# Follow_Line_Robot_Controller_Shematic.net
KiCad netlist of a schematic drawn in Altium Designer
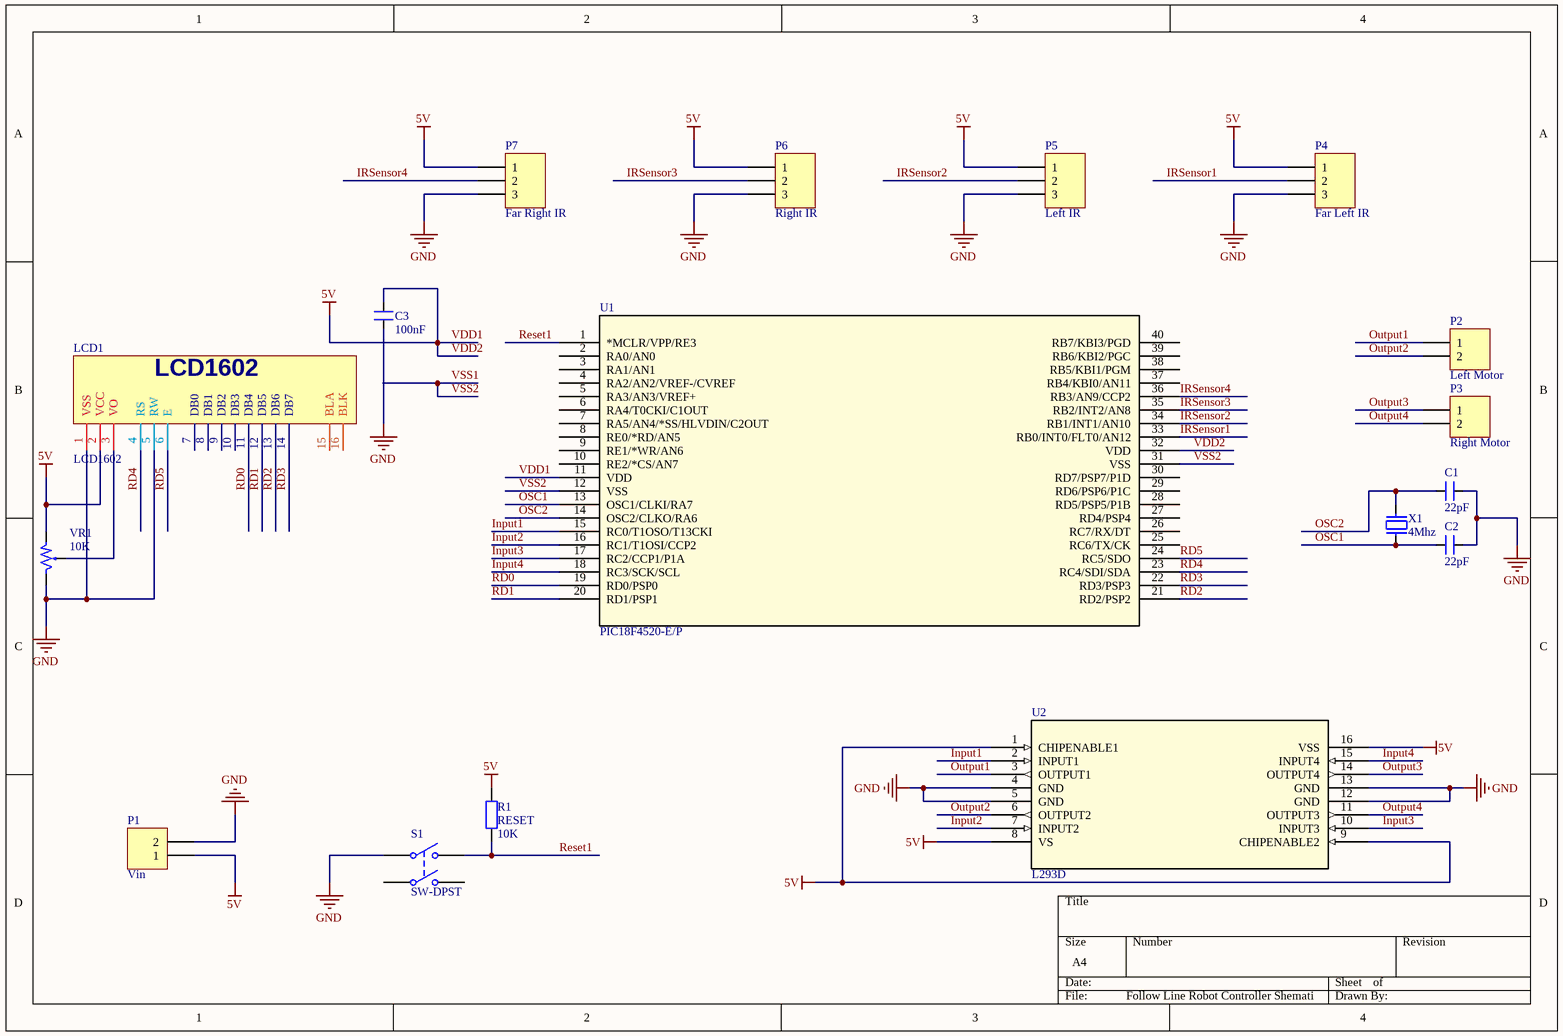
[diagram p0: Follow Line Robot Controller Shematic.SchDoc]

(export (version "E")
  (design (tool "Eeschema 10.0.6"))
  (components
    (comp (ref "C1")
      (value "22pF")
      (footprint "CN3")
      (description "Cap np W0.3")
      (fields (field (name "Comment") "Cap Cer"))
      (libsource (lib "Composants_Projet_Sheet_Full") (part "CN3"))
    )
    (comp (ref "C2")
      (value "22pF")
      (footprint "CN3")
      (description "Cap np W0.3")
      (fields (field (name "Comment") "Cap Cer"))
      (libsource (lib "Composants_Projet_Sheet_Full") (part "CN3"))
    )
    (comp (ref "C3")
      (value "100nF")
      (footprint "CN3")
      (description "Cap np W0.3")
      (fields (field (name "Comment") "Cap Cer"))
      (libsource (lib "Composants_Projet_Sheet_Full") (part "CN3"))
    )
    (comp (ref "LCD1")
      (value "LCD1602")
      (footprint "LCD1602")
      (libsource (lib "Composants_Projet_Sheet_Full") (part "LCD1602"))
    )
    (comp (ref "P1")
      (value "Vin")
      (footprint "HDR1X2")
      (description "Header, 2-Pin")
      (fields (field (name "PUBLISHER") "Altium Limited"))
      (libsource (lib "Composants_Projet_Sheet_Full") (part "Header 2"))
    )
    (comp (ref "P2")
      (value "Left Motor")
      (footprint "HDR1X2")
      (description "Header, 2-Pin")
      (fields (field (name "PUBLISHER") "Altium Limited"))
      (libsource (lib "") (part "Header 2_1"))
    )
    (comp (ref "P3")
      (value "Right Motor")
      (footprint "HDR1X2")
      (description "Header, 2-Pin")
      (fields (field (name "PUBLISHER") "Altium Limited"))
      (libsource (lib "") (part "Header 2_1"))
    )
    (comp (ref "P4")
      (value "Far Left IR")
      (footprint "HDR1X3")
      (description "Header, 3-Pin")
      (fields (field (name "PUBLISHER") "Altium Limited"))
      (libsource (lib "Composants_Projet_Sheet_Full") (part "Header 3"))
    )
    (comp (ref "P5")
      (value "Left IR")
      (footprint "HDR1X3")
      (description "Header, 3-Pin")
      (fields (field (name "PUBLISHER") "Altium Limited"))
      (libsource (lib "Composants_Projet_Sheet_Full") (part "Header 3"))
    )
    (comp (ref "P6")
      (value "Right IR")
      (footprint "HDR1X3")
      (description "Header, 3-Pin")
      (fields (field (name "PUBLISHER") "Altium Limited"))
      (libsource (lib "Composants_Projet_Sheet_Full") (part "Header 3"))
    )
    (comp (ref "P7")
      (value "Far Right IR")
      (footprint "HDR1X3")
      (description "Header, 3-Pin")
      (fields (field (name "PUBLISHER") "Altium Limited"))
      (libsource (lib "Composants_Projet_Sheet_Full") (part "Header 3"))
    )
    (comp (ref "R1")
      (value "RESET")
      (footprint "SMD R1206")
      (description "Resistor")
      (fields (field (name "ALTIUM_VALUE") "10K") (field (name "PUBLISHER") "Altium Limited"))
      (libsource (lib "Composants_Projet_Sheet_Full") (part "Res2_1"))
    )
    (comp (ref "S1")
      (value "SW-DPST")
      (footprint "DPST-4")
      (description "Double-Pole, Single-Throw Switch")
      (fields (field (name "PUBLISHER") "Altium Limited"))
      (libsource (lib "Composants_Projet_Sheet_Full") (part "SW-DPST"))
    )
    (comp (ref "U1")
      (value "PIC18F4520-E/P")
      (footprint "PDIP40_600MC_MCH")
      (description "No Description Available")
      (fields (field (name "COPYRIGHT") "Copyright (C) 2022 Ultra Librarian. All rights reserved."))
      (libsource (lib "PIC18F4520-E&slash_P") (part "PIC18F4520-E/P"))
    )
    (comp (ref "U2")
      (value "L293D")
      (footprint "PowerDIP-16_STM")
      (description "No Description Available")
      (fields (field (name "COPYRIGHT") "Copyright (C) 2022 Ultra Librarian. All rights reserved."))
      (libsource (lib "L293D") (part "L293D"))
    )
    (comp (ref "VR1")
      (value "10K")
      (footprint "VR")
      (description "Var Resistor")
      (libsource (lib "Composants_Projet_Sheet_Full") (part "VR1"))
    )
    (comp (ref "X1")
      (value "4Mhz")
      (footprint "XT2")
      (description "Crystal For all Crystal 2pin.")
      (libsource (lib "Composants_Projet_Sheet_Full") (part "XT2"))
    )
  )
  (nets
    (net (code "1") (name "/IRSensor1") (class "Default")
      (node (ref "P4") (pin "2") (pinfunction "2_2") (pintype "passive"))
      (node (ref "U1") (pin "33") (pinfunction "RB0/INT0/FLT0/AN12_33") (pintype "passive"))
    )
    (net (code "2") (name "/IRSensor2") (class "Default")
      (node (ref "P5") (pin "2") (pinfunction "2_2") (pintype "passive"))
      (node (ref "U1") (pin "34") (pinfunction "RB1/INT1/AN10_34") (pintype "passive"))
    )
    (net (code "3") (name "/IRSensor3") (class "Default")
      (node (ref "P6") (pin "2") (pinfunction "2_2") (pintype "passive"))
      (node (ref "U1") (pin "35") (pinfunction "RB2/INT2/AN8_35") (pintype "passive"))
    )
    (net (code "4") (name "/IRSensor4") (class "Default")
      (node (ref "P7") (pin "2") (pinfunction "2_2") (pintype "passive"))
      (node (ref "U1") (pin "36") (pinfunction "RB3/AN9/CCP2_36") (pintype "passive"))
    )
    (net (code "5") (name "/Input1") (class "Default")
      (node (ref "U1") (pin "15") (pinfunction "RC0/T1OSO/T13CKI_15") (pintype "passive"))
      (node (ref "U2") (pin "2") (pinfunction "INPUT1_2") (pintype "input"))
    )
    (net (code "6") (name "/Input2") (class "Default")
      (node (ref "U1") (pin "16") (pinfunction "RC1/T1OSI/CCP2_16") (pintype "passive"))
      (node (ref "U2") (pin "7") (pinfunction "INPUT2_7") (pintype "input"))
    )
    (net (code "7") (name "/Input3") (class "Default")
      (node (ref "U1") (pin "17") (pinfunction "RC2/CCP1/P1A_17") (pintype "passive"))
      (node (ref "U2") (pin "10") (pinfunction "INPUT3_10") (pintype "input"))
    )
    (net (code "8") (name "/Input4") (class "Default")
      (node (ref "U1") (pin "18") (pinfunction "RC3/SCK/SCL_18") (pintype "passive"))
      (node (ref "U2") (pin "15") (pinfunction "INPUT4_15") (pintype "input"))
    )
    (net (code "9") (name "/OSC1") (class "Default")
      (node (ref "C2") (pin "1") (pinfunction "1_1") (pintype "passive"))
      (node (ref "U1") (pin "13") (pinfunction "OSC1/CLKI/RA7_13") (pintype "passive"))
      (node (ref "X1") (pin "1") (pinfunction "1_1") (pintype "passive"))
    )
    (net (code "10") (name "/OSC2") (class "Default")
      (node (ref "C1") (pin "1") (pinfunction "1_1") (pintype "passive"))
      (node (ref "U1") (pin "14") (pinfunction "OSC2/CLKO/RA6_14") (pintype "passive"))
      (node (ref "X1") (pin "2") (pinfunction "2_2") (pintype "passive"))
    )
    (net (code "11") (name "/Output1") (class "Default")
      (node (ref "P2") (pin "1") (pinfunction "1_1") (pintype "passive"))
      (node (ref "U2") (pin "3") (pinfunction "OUTPUT1_3") (pintype "output"))
    )
    (net (code "12") (name "/Output2") (class "Default")
      (node (ref "P2") (pin "2") (pinfunction "2_2") (pintype "passive"))
      (node (ref "U2") (pin "6") (pinfunction "OUTPUT2_6") (pintype "output"))
    )
    (net (code "13") (name "/Output3") (class "Default")
      (node (ref "P3") (pin "1") (pinfunction "1_1") (pintype "passive"))
      (node (ref "U2") (pin "14") (pinfunction "OUTPUT4_14") (pintype "output"))
    )
    (net (code "14") (name "/Output4") (class "Default")
      (node (ref "P3") (pin "2") (pinfunction "2_2") (pintype "passive"))
      (node (ref "U2") (pin "11") (pinfunction "OUTPUT3_11") (pintype "output"))
    )
    (net (code "15") (name "/RD0") (class "Default")
      (node (ref "LCD1") (pin "11") (pinfunction "DB4_11") (pintype "passive"))
      (node (ref "U1") (pin "19") (pinfunction "RD0/PSP0_19") (pintype "passive"))
    )
    (net (code "16") (name "/RD1") (class "Default")
      (node (ref "LCD1") (pin "12") (pinfunction "DB5_12") (pintype "passive"))
      (node (ref "U1") (pin "20") (pinfunction "RD1/PSP1_20") (pintype "passive"))
    )
    (net (code "17") (name "/RD2") (class "Default")
      (node (ref "LCD1") (pin "13") (pinfunction "DB6_13") (pintype "passive"))
      (node (ref "U1") (pin "21") (pinfunction "RD2/PSP2_21") (pintype "passive"))
    )
    (net (code "18") (name "/RD3") (class "Default")
      (node (ref "LCD1") (pin "14") (pinfunction "DB7_14") (pintype "passive"))
      (node (ref "U1") (pin "22") (pinfunction "RD3/PSP3_22") (pintype "passive"))
    )
    (net (code "19") (name "/RD4") (class "Default")
      (node (ref "LCD1") (pin "4") (pinfunction "RS_4") (pintype "passive"))
      (node (ref "U1") (pin "23") (pinfunction "RC4/SDI/SDA_23") (pintype "passive"))
    )
    (net (code "20") (name "/RD5") (class "Default")
      (node (ref "LCD1") (pin "6") (pinfunction "E_6") (pintype "passive"))
      (node (ref "U1") (pin "24") (pinfunction "RC5/SDO_24") (pintype "passive"))
    )
    (net (code "21") (name "/Reset1") (class "Default")
      (node (ref "R1") (pin "1") (pinfunction "1_1") (pintype "passive"))
      (node (ref "S1") (pin "2") (pinfunction "NO1_2") (pintype "passive"))
      (node (ref "U1") (pin "1") (pinfunction "*MCLR/VPP/RE3_1") (pintype "passive"))
    )
    (net (code "22") (name "/VSS1") (class "Default")
      (node (ref "U1") (pin "12") (pinfunction "VSS_12") (pintype "passive"))
      (node (ref "U1") (pin "31") (pinfunction "VSS_31") (pintype "passive"))
    )
    (net (code "23") (name "5V") (class "Default")
      (node (ref "C3") (pin "2") (pinfunction "2_2") (pintype "passive"))
      (node (ref "LCD1") (pin "2") (pinfunction "VCC_2") (pintype "passive"))
      (node (ref "P1") (pin "1") (pinfunction "1_1") (pintype "passive"))
      (node (ref "P4") (pin "1") (pinfunction "1_1") (pintype "passive"))
      (node (ref "P5") (pin "1") (pinfunction "1_1") (pintype "passive"))
      (node (ref "P6") (pin "1") (pinfunction "1_1") (pintype "passive"))
      (node (ref "P7") (pin "1") (pinfunction "1_1") (pintype "passive"))
      (node (ref "R1") (pin "2") (pinfunction "2_2") (pintype "passive"))
      (node (ref "U1") (pin "11") (pinfunction "VDD_11") (pintype "passive"))
      (node (ref "U1") (pin "32") (pinfunction "VDD_32") (pintype "passive"))
      (node (ref "U2") (pin "1") (pinfunction "CHIPENABLE1_1") (pintype "input"))
      (node (ref "U2") (pin "16") (pinfunction "VSS_16") (pintype "power_in"))
      (node (ref "U2") (pin "8") (pinfunction "VS_8") (pintype "power_in"))
      (node (ref "U2") (pin "9") (pinfunction "CHIPENABLE2_9") (pintype "input"))
      (node (ref "VR1") (pin "1") (pinfunction "1_1") (pintype "passive"))
    )
    (net (code "24") (name "GND") (class "Default")
      (node (ref "C1") (pin "2") (pinfunction "2_2") (pintype "passive"))
      (node (ref "C2") (pin "2") (pinfunction "2_2") (pintype "passive"))
      (node (ref "C3") (pin "1") (pinfunction "1_1") (pintype "passive"))
      (node (ref "LCD1") (pin "1") (pinfunction "VSS_1") (pintype "passive"))
      (node (ref "LCD1") (pin "5") (pinfunction "RW_5") (pintype "passive"))
      (node (ref "P1") (pin "2") (pinfunction "2_2") (pintype "passive"))
      (node (ref "P4") (pin "3") (pinfunction "3_3") (pintype "passive"))
      (node (ref "P5") (pin "3") (pinfunction "3_3") (pintype "passive"))
      (node (ref "P6") (pin "3") (pinfunction "3_3") (pintype "passive"))
      (node (ref "P7") (pin "3") (pinfunction "3_3") (pintype "passive"))
      (node (ref "S1") (pin "1") (pinfunction "COMMON1_1") (pintype "passive"))
      (node (ref "U2") (pin "12") (pinfunction "GND_12") (pintype "passive"))
      (node (ref "U2") (pin "13") (pinfunction "GND_13") (pintype "passive"))
      (node (ref "U2") (pin "4") (pinfunction "GND_4") (pintype "passive"))
      (node (ref "U2") (pin "5") (pinfunction "GND_5") (pintype "passive"))
      (node (ref "VR1") (pin "3") (pinfunction "3_3") (pintype "passive"))
    )
    (net (code "25") (name "Net-(LCD1-VO)") (class "Default")
      (node (ref "LCD1") (pin "3") (pinfunction "VO_3") (pintype "passive"))
      (node (ref "VR1") (pin "2") (pinfunction "2_2") (pintype "passive"))
    )
    (net (code "26") (name "unconnected-(LCD1-BLA-Pad15)") (class "Default")
      (node (ref "LCD1") (pin "15") (pinfunction "BLA_15") (pintype "passive"))
    )
    (net (code "27") (name "unconnected-(LCD1-BLK-Pad16)") (class "Default")
      (node (ref "LCD1") (pin "16") (pinfunction "BLK_16") (pintype "passive"))
    )
    (net (code "28") (name "unconnected-(LCD1-DB0-Pad7)") (class "Default")
      (node (ref "LCD1") (pin "7") (pinfunction "DB0_7") (pintype "passive"))
    )
    (net (code "29") (name "unconnected-(LCD1-DB1-Pad8)") (class "Default")
      (node (ref "LCD1") (pin "8") (pinfunction "DB1_8") (pintype "passive"))
    )
    (net (code "30") (name "unconnected-(LCD1-DB2-Pad9)") (class "Default")
      (node (ref "LCD1") (pin "9") (pinfunction "DB2_9") (pintype "passive"))
    )
    (net (code "31") (name "unconnected-(LCD1-DB3-Pad10)") (class "Default")
      (node (ref "LCD1") (pin "10") (pinfunction "DB3_10") (pintype "passive"))
    )
    (net (code "32") (name "unconnected-(S1-COMMON2-Pad3)") (class "Default")
      (node (ref "S1") (pin "3") (pinfunction "COMMON2_3") (pintype "passive"))
    )
    (net (code "33") (name "unconnected-(S1-NO2-Pad4)") (class "Default")
      (node (ref "S1") (pin "4") (pinfunction "NO2_4") (pintype "passive"))
    )
    (net (code "34") (name "unconnected-(U1-RA0{slash}AN0-Pad2)") (class "Default")
      (node (ref "U1") (pin "2") (pinfunction "RA0/AN0_2") (pintype "passive"))
    )
    (net (code "35") (name "unconnected-(U1-RA1{slash}AN1-Pad3)") (class "Default")
      (node (ref "U1") (pin "3") (pinfunction "RA1/AN1_3") (pintype "passive"))
    )
    (net (code "36") (name "unconnected-(U1-RA2{slash}AN2{slash}VREF-{slash}CVREF-Pad4)") (class "Default")
      (node (ref "U1") (pin "4") (pinfunction "RA2/AN2/VREF-/CVREF_4") (pintype "passive"))
    )
    (net (code "37") (name "unconnected-(U1-RA3{slash}AN3{slash}VREF+-Pad5)") (class "Default")
      (node (ref "U1") (pin "5") (pinfunction "RA3/AN3/VREF+_5") (pintype "passive"))
    )
    (net (code "38") (name "unconnected-(U1-RA4{slash}T0CKI{slash}C1OUT-Pad6)") (class "Default")
      (node (ref "U1") (pin "6") (pinfunction "RA4/T0CKI/C1OUT_6") (pintype "passive"))
    )
    (net (code "39") (name "unconnected-(U1-RA5{slash}AN4{slash}*SS{slash}HLVDIN{slash}C2OUT-Pad7)") (class "Default")
      (node (ref "U1") (pin "7") (pinfunction "RA5/AN4/*SS/HLVDIN/C2OUT_7") (pintype "passive"))
    )
    (net (code "40") (name "unconnected-(U1-RB4{slash}KBI0{slash}AN11-Pad37)") (class "Default")
      (node (ref "U1") (pin "37") (pinfunction "RB4/KBI0/AN11_37") (pintype "passive"))
    )
    (net (code "41") (name "unconnected-(U1-RB5{slash}KBI1{slash}PGM-Pad38)") (class "Default")
      (node (ref "U1") (pin "38") (pinfunction "RB5/KBI1/PGM_38") (pintype "passive"))
    )
    (net (code "42") (name "unconnected-(U1-RB6{slash}KBI2{slash}PGC-Pad39)") (class "Default")
      (node (ref "U1") (pin "39") (pinfunction "RB6/KBI2/PGC_39") (pintype "passive"))
    )
    (net (code "43") (name "unconnected-(U1-RB7{slash}KBI3{slash}PGD-Pad40)") (class "Default")
      (node (ref "U1") (pin "40") (pinfunction "RB7/KBI3/PGD_40") (pintype "passive"))
    )
    (net (code "44") (name "unconnected-(U1-RC6{slash}TX{slash}CK-Pad25)") (class "Default")
      (node (ref "U1") (pin "25") (pinfunction "RC6/TX/CK_25") (pintype "passive"))
    )
    (net (code "45") (name "unconnected-(U1-RC7{slash}RX{slash}DT-Pad26)") (class "Default")
      (node (ref "U1") (pin "26") (pinfunction "RC7/RX/DT_26") (pintype "passive"))
    )
    (net (code "46") (name "unconnected-(U1-RD4{slash}PSP4-Pad27)") (class "Default")
      (node (ref "U1") (pin "27") (pinfunction "RD4/PSP4_27") (pintype "passive"))
    )
    (net (code "47") (name "unconnected-(U1-RD5{slash}PSP5{slash}P1B-Pad28)") (class "Default")
      (node (ref "U1") (pin "28") (pinfunction "RD5/PSP5/P1B_28") (pintype "passive"))
    )
    (net (code "48") (name "unconnected-(U1-RD6{slash}PSP6{slash}P1C-Pad29)") (class "Default")
      (node (ref "U1") (pin "29") (pinfunction "RD6/PSP6/P1C_29") (pintype "passive"))
    )
    (net (code "49") (name "unconnected-(U1-RD7{slash}PSP7{slash}P1D-Pad30)") (class "Default")
      (node (ref "U1") (pin "30") (pinfunction "RD7/PSP7/P1D_30") (pintype "passive"))
    )
    (net (code "50") (name "unconnected-(U1-RE0{slash}*RD{slash}AN5-Pad8)") (class "Default")
      (node (ref "U1") (pin "8") (pinfunction "RE0/*RD/AN5_8") (pintype "passive"))
    )
    (net (code "51") (name "unconnected-(U1-RE1{slash}*WR{slash}AN6-Pad9)") (class "Default")
      (node (ref "U1") (pin "9") (pinfunction "RE1/*WR/AN6_9") (pintype "passive"))
    )
    (net (code "52") (name "unconnected-(U1-RE2{slash}*CS{slash}AN7-Pad10)") (class "Default")
      (node (ref "U1") (pin "10") (pinfunction "RE2/*CS/AN7_10") (pintype "passive"))
    )
  )
)
